# ibee.net
KiCad netlist of a schematic drawn in EAGLE
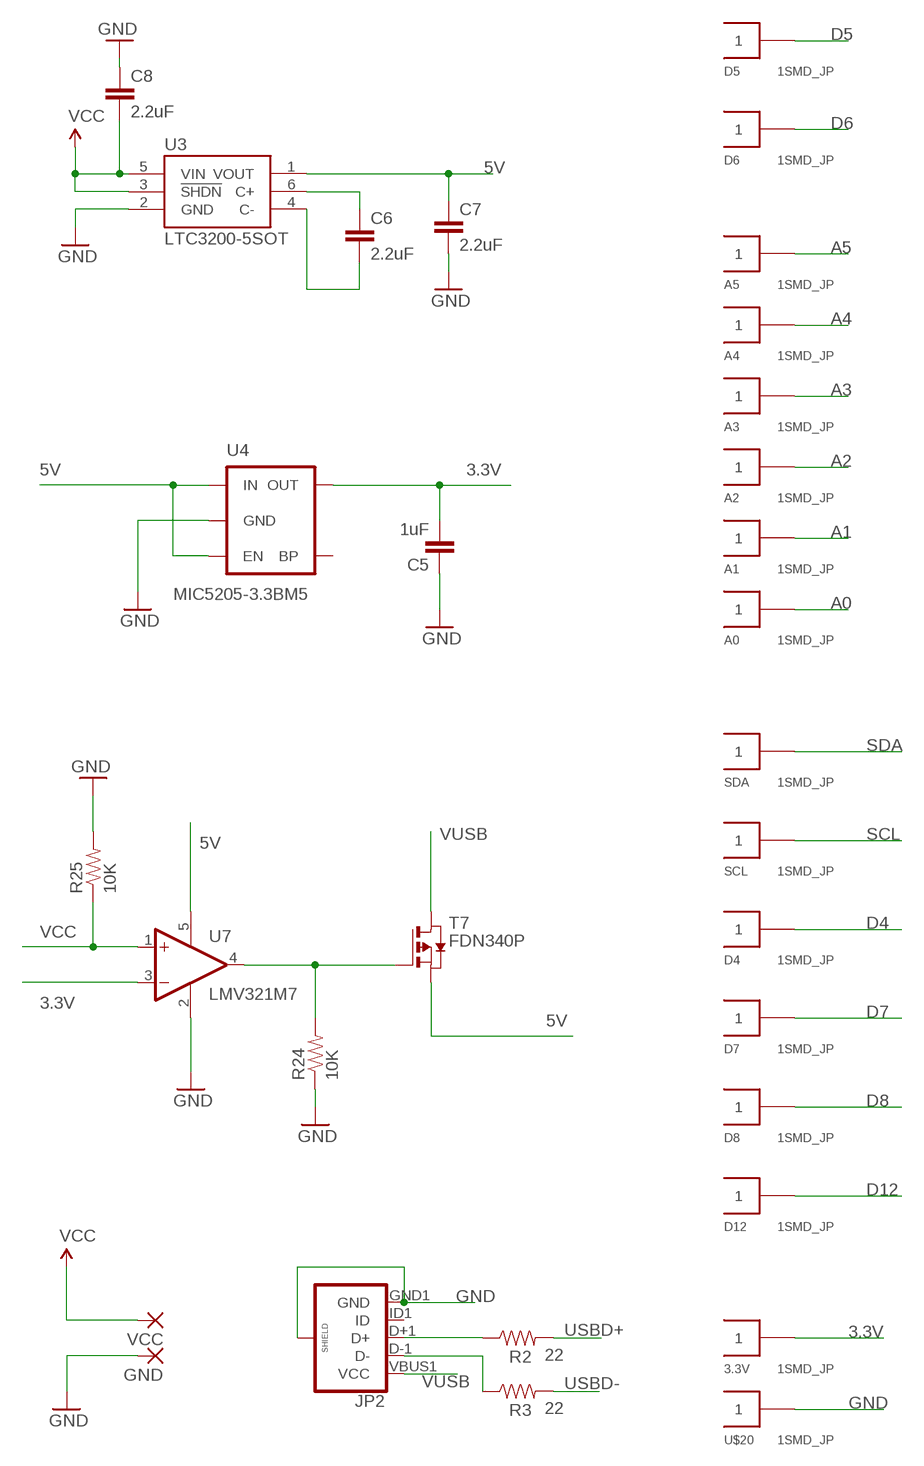
[diagram p0: schematic, sheet 1, part 1 of 2]
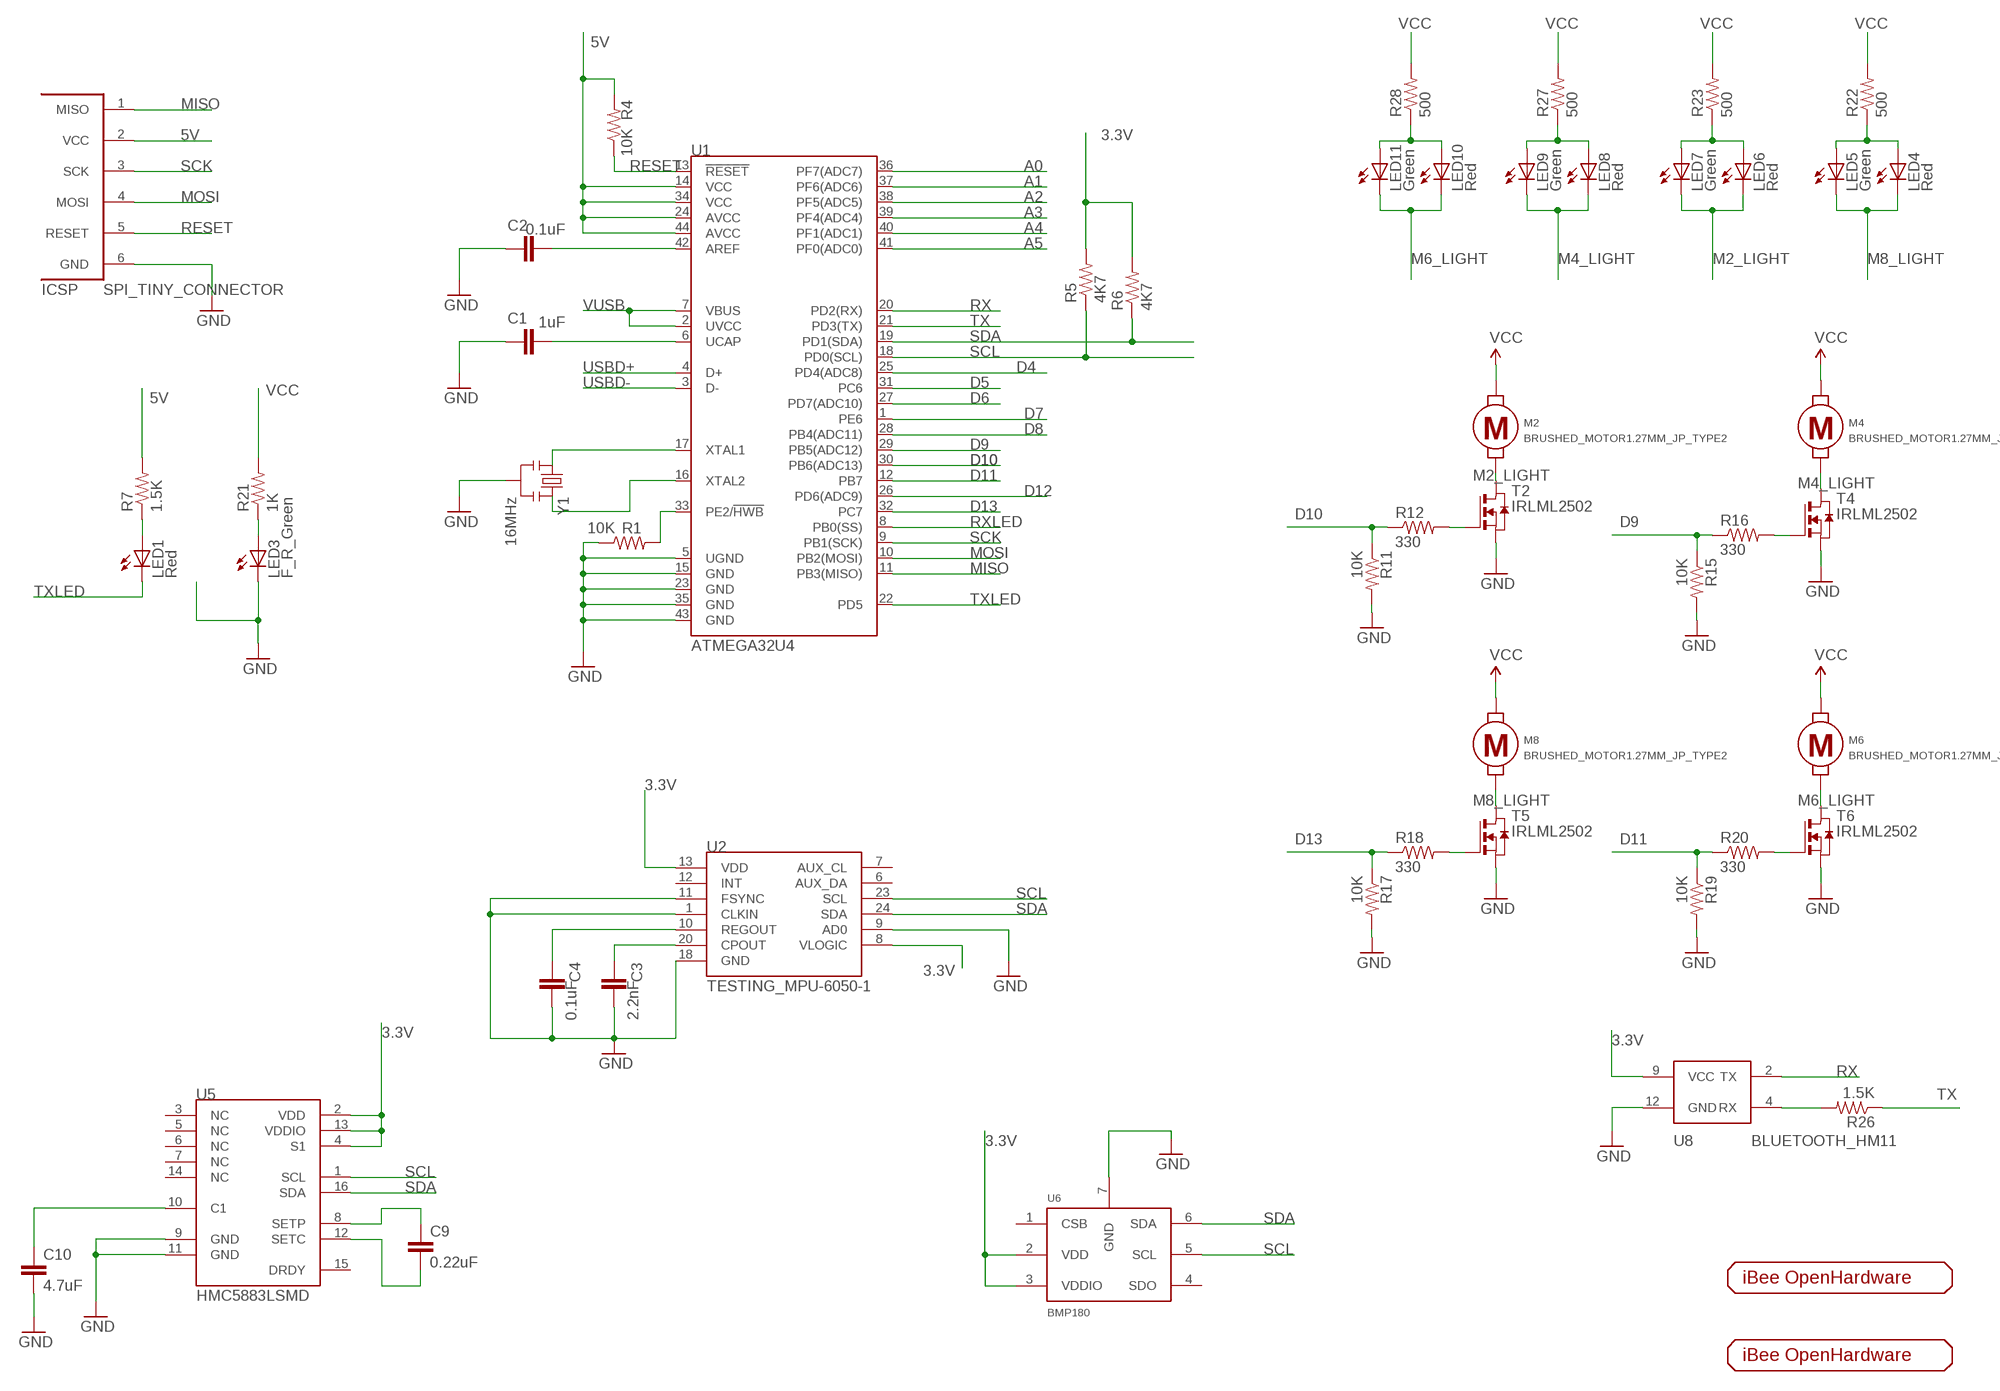
[diagram p1: schematic, sheet 1, part 2 of 2]

(export (version "E")
  (design (tool "Eeschema 10.0.6"))
  (components
    (comp (ref "3.3V")
      (value "1SMD_JP")
      (footprint "eagle-import:1SMD")
      (libsource (lib "eagle-import") (part "1SMD_JP"))
    )
    (comp (ref "A0")
      (value "1SMD_JP")
      (footprint "eagle-import:1SMD")
      (libsource (lib "eagle-import") (part "1SMD_JP"))
    )
    (comp (ref "A1")
      (value "1SMD_JP")
      (footprint "eagle-import:1SMD")
      (libsource (lib "eagle-import") (part "1SMD_JP"))
    )
    (comp (ref "A2")
      (value "1SMD_JP")
      (footprint "eagle-import:1SMD")
      (libsource (lib "eagle-import") (part "1SMD_JP"))
    )
    (comp (ref "A3")
      (value "1SMD_JP")
      (footprint "eagle-import:1SMD")
      (libsource (lib "eagle-import") (part "1SMD_JP"))
    )
    (comp (ref "A4")
      (value "1SMD_JP")
      (footprint "eagle-import:1SMD")
      (libsource (lib "eagle-import") (part "1SMD_JP"))
    )
    (comp (ref "A5")
      (value "1SMD_JP")
      (footprint "eagle-import:1SMD")
      (libsource (lib "eagle-import") (part "1SMD_JP"))
    )
    (comp (ref "C1")
      (value "1uF")
      (footprint "eagle-import:0402-CAP")
      (libsource (lib "eagle-import") (part "CAP0402-CAP"))
    )
    (comp (ref "C2")
      (value "0.1uF")
      (footprint "eagle-import:0402-CAP")
      (libsource (lib "eagle-import") (part "CAP0402-CAP"))
    )
    (comp (ref "C3")
      (value "2.2nF")
      (footprint "eagle-import:0402-CAP")
      (libsource (lib "eagle-import") (part "CAP0402-CAP"))
    )
    (comp (ref "C4")
      (value "0.1uF")
      (footprint "eagle-import:0402-CAP")
      (libsource (lib "eagle-import") (part "CAP0402-CAP"))
    )
    (comp (ref "C5")
      (value "1uF")
      (footprint "eagle-import:0402-CAP")
      (libsource (lib "eagle-import") (part "CAP0402-CAP"))
    )
    (comp (ref "C6")
      (value "2.2uF")
      (footprint "eagle-import:0603-CAP")
      (libsource (lib "eagle-import") (part "CAP0603-CAP"))
    )
    (comp (ref "C7")
      (value "2.2uF")
      (footprint "eagle-import:0603-CAP")
      (libsource (lib "eagle-import") (part "CAP0603-CAP"))
    )
    (comp (ref "C8")
      (value "2.2uF")
      (footprint "eagle-import:0603-CAP")
      (libsource (lib "eagle-import") (part "CAP0603-CAP"))
    )
    (comp (ref "C9")
      (value "0.22uF")
      (footprint "eagle-import:0402-CAP")
      (libsource (lib "eagle-import") (part "CAP0402-CAP"))
    )
    (comp (ref "C10")
      (value "4.7uF")
      (footprint "eagle-import:0603-CAP")
      (libsource (lib "eagle-import") (part "CAP0603-CAP"))
    )
    (comp (ref "D4")
      (value "1SMD_JP")
      (footprint "eagle-import:1SMD")
      (libsource (lib "eagle-import") (part "1SMD_JP"))
    )
    (comp (ref "D5")
      (value "1SMD_JP")
      (footprint "eagle-import:1SMD")
      (libsource (lib "eagle-import") (part "1SMD_JP"))
    )
    (comp (ref "D6")
      (value "1SMD_JP")
      (footprint "eagle-import:1SMD")
      (libsource (lib "eagle-import") (part "1SMD_JP"))
    )
    (comp (ref "D7")
      (value "1SMD_JP")
      (footprint "eagle-import:1SMD")
      (libsource (lib "eagle-import") (part "1SMD_JP"))
    )
    (comp (ref "D8")
      (value "1SMD_JP")
      (footprint "eagle-import:1SMD")
      (libsource (lib "eagle-import") (part "1SMD_JP"))
    )
    (comp (ref "D12")
      (value "1SMD_JP")
      (footprint "eagle-import:1SMD")
      (libsource (lib "eagle-import") (part "1SMD_JP"))
    )
    (comp (ref "GND")
      (value "2,15/1,0")
      (footprint "eagle-import:2,15_1,0")
      (libsource (lib "eagle-import") (part "2,15/1,0"))
    )
    (comp (ref "ICSP")
      (value "SPI_TINY_CONNECTOR")
      (footprint "eagle-import:AVR_ISP_TINY_CONNECTOR_NO_BORDER")
      (libsource (lib "eagle-import") (part "AVR_ISP_TINY_CONNECTORAVR_ISP_TINY_CONNCTOR_NO_BORDER"))
    )
    (comp (ref "JP2")
      (value "USB_MICROB_PLUGCONN-11752")
      (footprint "eagle-import:USB-B-MICRO-SMD_V03")
      (libsource (lib "eagle-import") (part "USB_MICROB_PLUGCONN-11752"))
    )
    (comp (ref "LED1")
      (value "Red")
      (footprint "eagle-import:CHIPLED_0603")
      (libsource (lib "eagle-import") (part "LEDCHIPLED_0603"))
    )
    (comp (ref "LED3")
      (value "F_R_Green")
      (footprint "eagle-import:CHIPLED_0603")
      (libsource (lib "eagle-import") (part "LEDCHIPLED_0603"))
    )
    (comp (ref "LED4")
      (value "Red")
      (footprint "eagle-import:CHIPLED_0603")
      (libsource (lib "eagle-import") (part "LEDCHIPLED_0603"))
    )
    (comp (ref "LED5")
      (value "Green")
      (footprint "eagle-import:CHIPLED_0603")
      (libsource (lib "eagle-import") (part "LEDCHIPLED_0603"))
    )
    (comp (ref "LED6")
      (value "Red")
      (footprint "eagle-import:CHIPLED_0603")
      (libsource (lib "eagle-import") (part "LEDCHIPLED_0603"))
    )
    (comp (ref "LED7")
      (value "Green")
      (footprint "eagle-import:CHIPLED_0603")
      (libsource (lib "eagle-import") (part "LEDCHIPLED_0603"))
    )
    (comp (ref "LED8")
      (value "Red")
      (footprint "eagle-import:CHIPLED_0603")
      (libsource (lib "eagle-import") (part "LEDCHIPLED_0603"))
    )
    (comp (ref "LED9")
      (value "Green")
      (footprint "eagle-import:CHIPLED_0603")
      (libsource (lib "eagle-import") (part "LEDCHIPLED_0603"))
    )
    (comp (ref "LED10")
      (value "Red")
      (footprint "eagle-import:CHIPLED_0603")
      (libsource (lib "eagle-import") (part "LEDCHIPLED_0603"))
    )
    (comp (ref "LED11")
      (value "Green")
      (footprint "eagle-import:CHIPLED_0603")
      (libsource (lib "eagle-import") (part "LEDCHIPLED_0603"))
    )
    (comp (ref "M2")
      (value "BRUSHED_MOTOR1.27MM_JP_TYPE2")
      (footprint "eagle-import:BRUSHED_MOTOR_1.27MM_JP_TYPE2")
      (libsource (lib "eagle-import") (part "BRUSHED_MOTOR1.27MM_JP_TYPE2"))
    )
    (comp (ref "M4")
      (value "BRUSHED_MOTOR1.27MM_JP")
      (footprint "eagle-import:BRUSHED_MOTOR_1.27MM_JP")
      (libsource (lib "eagle-import") (part "BRUSHED_MOTOR1.27MM_JP"))
    )
    (comp (ref "M6")
      (value "BRUSHED_MOTOR1.27MM_JP")
      (footprint "eagle-import:BRUSHED_MOTOR_1.27MM_JP")
      (libsource (lib "eagle-import") (part "BRUSHED_MOTOR1.27MM_JP"))
    )
    (comp (ref "M8")
      (value "BRUSHED_MOTOR1.27MM_JP_TYPE2")
      (footprint "eagle-import:BRUSHED_MOTOR_1.27MM_JP_TYPE2")
      (libsource (lib "eagle-import") (part "BRUSHED_MOTOR1.27MM_JP_TYPE2"))
    )
    (comp (ref "R1")
      (value "10K")
      (footprint "eagle-import:0402-RES")
      (libsource (lib "eagle-import") (part "RESISTOR0402-RES"))
    )
    (comp (ref "R2")
      (value "22")
      (footprint "eagle-import:0402-RES")
      (libsource (lib "eagle-import") (part "RESISTOR0402-RES"))
    )
    (comp (ref "R3")
      (value "22")
      (footprint "eagle-import:0402-RES")
      (libsource (lib "eagle-import") (part "RESISTOR0402-RES"))
    )
    (comp (ref "R4")
      (value "10K")
      (footprint "eagle-import:0402-RES")
      (libsource (lib "eagle-import") (part "RESISTOR0402-RES"))
    )
    (comp (ref "R5")
      (value "4K7")
      (footprint "eagle-import:0402-RES")
      (libsource (lib "eagle-import") (part "RESISTOR0402-RES"))
    )
    (comp (ref "R6")
      (value "4K7")
      (footprint "eagle-import:0402-RES")
      (libsource (lib "eagle-import") (part "RESISTOR0402-RES"))
    )
    (comp (ref "R7")
      (value "1.5K")
      (footprint "eagle-import:0402-RES")
      (libsource (lib "eagle-import") (part "RESISTOR0402-RES"))
    )
    (comp (ref "R11")
      (value "10K")
      (footprint "eagle-import:0402-RES")
      (libsource (lib "eagle-import") (part "RESISTOR0402-RES"))
    )
    (comp (ref "R12")
      (value "330")
      (footprint "eagle-import:0402-RES")
      (libsource (lib "eagle-import") (part "RESISTOR0402-RES"))
    )
    (comp (ref "R15")
      (value "10K")
      (footprint "eagle-import:0402-RES")
      (libsource (lib "eagle-import") (part "RESISTOR0402-RES"))
    )
    (comp (ref "R16")
      (value "330")
      (footprint "eagle-import:0402-RES")
      (libsource (lib "eagle-import") (part "RESISTOR0402-RES"))
    )
    (comp (ref "R17")
      (value "10K")
      (footprint "eagle-import:0402-RES")
      (libsource (lib "eagle-import") (part "RESISTOR0402-RES"))
    )
    (comp (ref "R18")
      (value "330")
      (footprint "eagle-import:0402-RES")
      (libsource (lib "eagle-import") (part "RESISTOR0402-RES"))
    )
    (comp (ref "R19")
      (value "10K")
      (footprint "eagle-import:0402-RES")
      (libsource (lib "eagle-import") (part "RESISTOR0402-RES"))
    )
    (comp (ref "R20")
      (value "330")
      (footprint "eagle-import:0402-RES")
      (libsource (lib "eagle-import") (part "RESISTOR0402-RES"))
    )
    (comp (ref "R21")
      (value "1K")
      (footprint "eagle-import:0402-RES")
      (libsource (lib "eagle-import") (part "RESISTOR0402-RES"))
    )
    (comp (ref "R22")
      (value "500")
      (footprint "eagle-import:0402-RES")
      (libsource (lib "eagle-import") (part "RESISTOR0402-RES"))
    )
    (comp (ref "R23")
      (value "500")
      (footprint "eagle-import:0402-RES")
      (libsource (lib "eagle-import") (part "RESISTOR0402-RES"))
    )
    (comp (ref "R24")
      (value "10K")
      (footprint "eagle-import:0402-RES")
      (libsource (lib "eagle-import") (part "RESISTOR0402-RES"))
    )
    (comp (ref "R25")
      (value "10K")
      (footprint "eagle-import:0402-RES")
      (libsource (lib "eagle-import") (part "RESISTOR0402-RES"))
    )
    (comp (ref "R26")
      (value "1.5K")
      (footprint "eagle-import:0402-RES")
      (libsource (lib "eagle-import") (part "RESISTOR0402-RES"))
    )
    (comp (ref "R27")
      (value "500")
      (footprint "eagle-import:0402-RES")
      (libsource (lib "eagle-import") (part "RESISTOR0402-RES"))
    )
    (comp (ref "R28")
      (value "500")
      (footprint "eagle-import:0402-RES")
      (libsource (lib "eagle-import") (part "RESISTOR0402-RES"))
    )
    (comp (ref "SCL")
      (value "1SMD_JP")
      (footprint "eagle-import:1SMD")
      (libsource (lib "eagle-import") (part "1SMD_JP"))
    )
    (comp (ref "SDA")
      (value "1SMD_JP")
      (footprint "eagle-import:1SMD")
      (libsource (lib "eagle-import") (part "1SMD_JP"))
    )
    (comp (ref "T2")
      (value "IRLML2502")
      (footprint "eagle-import:SOT-23")
      (libsource (lib "eagle-import") (part "NMOSSOT23"))
    )
    (comp (ref "T4")
      (value "IRLML2502")
      (footprint "eagle-import:SOT-23")
      (libsource (lib "eagle-import") (part "NMOSSOT23"))
    )
    (comp (ref "T5")
      (value "IRLML2502")
      (footprint "eagle-import:SOT-23")
      (libsource (lib "eagle-import") (part "NMOSSOT23"))
    )
    (comp (ref "T6")
      (value "IRLML2502")
      (footprint "eagle-import:SOT-23")
      (libsource (lib "eagle-import") (part "NMOSSOT23"))
    )
    (comp (ref "T7")
      (value "FDN340P")
      (footprint "eagle-import:SOT23")
      (libsource (lib "eagle-import") (part "FDN340P"))
    )
    (comp (ref "U$1")
      (value "IBEE-LOGO-T")
      (footprint "eagle-import:IBEE-LOGO-TOP")
      (libsource (lib "eagle-import") (part "IBEE-LOGO-T"))
    )
    (comp (ref "U$2")
      (value "IBEE-LOGO-B")
      (footprint "eagle-import:FLEXBOT_LOGO_TYPE2")
      (libsource (lib "eagle-import") (part "IBEE-LOGO-B"))
    )
    (comp (ref "U$20")
      (value "1SMD_JP")
      (footprint "eagle-import:1SMD")
      (libsource (lib "eagle-import") (part "1SMD_JP"))
    )
    (comp (ref "U1")
      (value "ATMEGA32U4")
      (footprint "eagle-import:TESTING_QFN-44-7X7")
      (libsource (lib "eagle-import") (part "ATMEGA32U4"))
    )
    (comp (ref "U2")
      (value "TESTING_MPU-6050-1")
      (footprint "eagle-import:TESTING_QFN-24-4MM2")
      (libsource (lib "eagle-import") (part "TESTING_MPU-6050-1"))
    )
    (comp (ref "U3")
      (value "LTC3200-5SOT")
      (footprint "eagle-import:SOT23-6")
      (libsource (lib "eagle-import") (part "LTC3200-5SOT"))
    )
    (comp (ref "U4")
      (value "MIC5205-3.3BM5")
      (footprint "eagle-import:SOT23-5")
      (libsource (lib "eagle-import") (part "MIC52053.3V"))
    )
    (comp (ref "U5")
      (value "HMC5883LSMD")
      (footprint "eagle-import:TESTING_16LPCC")
      (libsource (lib "eagle-import") (part "HMC5883LSMD"))
    )
    (comp (ref "U6")
      (value "BMP180")
      (footprint "eagle-import:BMP180")
      (libsource (lib "eagle-import") (part "BMP180"))
    )
    (comp (ref "U7")
      (value "LMV321M7")
      (footprint "eagle-import:SC70-5L")
      (libsource (lib "eagle-import") (part "LMV321?M7"))
    )
    (comp (ref "U8")
      (value "BLUETOOTH_HM11")
      (footprint "eagle-import:BLUETOOTH_HM11")
      (libsource (lib "eagle-import") (part "BLUETOOTH_HM11"))
    )
    (comp (ref "VCC")
      (value "2,15/1,0")
      (footprint "eagle-import:2,15_1,0")
      (libsource (lib "eagle-import") (part "2,15/1,0"))
    )
    (comp (ref "Y1")
      (value "16MHz")
      (footprint "eagle-import:RESONATOR-SMD")
      (libsource (lib "eagle-import") (part "RESONATOR16MHZ"))
    )
  )
  (nets
    (net (code "1") (name "/3.3V") (class "Default")
      (node (ref "3.3V") (pin "1") (pinfunction "1_1") (pintype "bidirectional"))
      (node (ref "C5") (pin "2") (pinfunction "2_2") (pintype "passive"))
      (node (ref "R5") (pin "2") (pinfunction "2_2") (pintype "passive"))
      (node (ref "R6") (pin "2") (pinfunction "2_2") (pintype "passive"))
      (node (ref "U2") (pin "13") (pinfunction "VDD_13") (pintype "bidirectional"))
      (node (ref "U2") (pin "8") (pinfunction "VLOGIC_8") (pintype "bidirectional"))
      (node (ref "U4") (pin "5") (pinfunction "OUT_5") (pintype "passive"))
      (node (ref "U5") (pin "13") (pinfunction "VDDIO_13") (pintype "bidirectional"))
      (node (ref "U5") (pin "2") (pinfunction "VDD_2") (pintype "bidirectional"))
      (node (ref "U5") (pin "4") (pinfunction "S1_4") (pintype "bidirectional"))
      (node (ref "U6") (pin "2") (pinfunction "VDD_2") (pintype "bidirectional"))
      (node (ref "U6") (pin "3") (pinfunction "VDDIO_3") (pintype "bidirectional"))
      (node (ref "U7") (pin "3") (pinfunction "-IN_3") (pintype "input"))
      (node (ref "U8") (pin "9") (pinfunction "VCC_9") (pintype "bidirectional"))
    )
    (net (code "2") (name "/5V") (class "Default")
      (node (ref "C7") (pin "1") (pinfunction "1_1") (pintype "passive"))
      (node (ref "ICSP") (pin "2") (pinfunction "VCC_2") (pintype "bidirectional"))
      (node (ref "R4") (pin "2") (pinfunction "2_2") (pintype "passive"))
      (node (ref "R7") (pin "2") (pinfunction "2_2") (pintype "passive"))
      (node (ref "T7") (pin "2") (pinfunction "S_2") (pintype "passive"))
      (node (ref "U1") (pin "14") (pinfunction "VCC_14") (pintype "bidirectional"))
      (node (ref "U1") (pin "24") (pinfunction "AVCC_24") (pintype "bidirectional"))
      (node (ref "U1") (pin "34") (pinfunction "VCC_34") (pintype "bidirectional"))
      (node (ref "U1") (pin "44") (pinfunction "AVCC_44") (pintype "bidirectional"))
      (node (ref "U3") (pin "1") (pinfunction "VOUT_1") (pintype "bidirectional"))
      (node (ref "U4") (pin "1") (pinfunction "IN_1") (pintype "input"))
      (node (ref "U4") (pin "3") (pinfunction "EN_3") (pintype "input"))
      (node (ref "U7") (pin "5") (pinfunction "V+_5") (pintype "power_in"))
    )
    (net (code "3") (name "/A0") (class "Default")
      (node (ref "A0") (pin "1") (pinfunction "1_1") (pintype "bidirectional"))
      (node (ref "U1") (pin "36") (pinfunction "PF7(ADC7)_36") (pintype "bidirectional"))
    )
    (net (code "4") (name "/A1") (class "Default")
      (node (ref "A1") (pin "1") (pinfunction "1_1") (pintype "bidirectional"))
      (node (ref "U1") (pin "37") (pinfunction "PF6(ADC6)_37") (pintype "bidirectional"))
    )
    (net (code "5") (name "/A2") (class "Default")
      (node (ref "A2") (pin "1") (pinfunction "1_1") (pintype "bidirectional"))
      (node (ref "U1") (pin "38") (pinfunction "PF5(ADC5)_38") (pintype "bidirectional"))
    )
    (net (code "6") (name "/A3") (class "Default")
      (node (ref "A3") (pin "1") (pinfunction "1_1") (pintype "bidirectional"))
      (node (ref "U1") (pin "39") (pinfunction "PF4(ADC4)_39") (pintype "bidirectional"))
    )
    (net (code "7") (name "/A4") (class "Default")
      (node (ref "A4") (pin "1") (pinfunction "1_1") (pintype "bidirectional"))
      (node (ref "U1") (pin "40") (pinfunction "PF1(ADC1)_40") (pintype "bidirectional"))
    )
    (net (code "8") (name "/A5") (class "Default")
      (node (ref "A5") (pin "1") (pinfunction "1_1") (pintype "bidirectional"))
      (node (ref "U1") (pin "41") (pinfunction "PF0(ADC0)_41") (pintype "bidirectional"))
    )
    (net (code "9") (name "/D4") (class "Default")
      (node (ref "D4") (pin "1") (pinfunction "1_1") (pintype "bidirectional"))
      (node (ref "U1") (pin "25") (pinfunction "PD4(ADC8)_25") (pintype "bidirectional"))
    )
    (net (code "10") (name "/D5") (class "Default")
      (node (ref "D5") (pin "1") (pinfunction "1_1") (pintype "bidirectional"))
      (node (ref "U1") (pin "31") (pinfunction "PC6_31") (pintype "bidirectional"))
    )
    (net (code "11") (name "/D6") (class "Default")
      (node (ref "D6") (pin "1") (pinfunction "1_1") (pintype "bidirectional"))
      (node (ref "U1") (pin "27") (pinfunction "PD7(ADC10)_27") (pintype "bidirectional"))
    )
    (net (code "12") (name "/D7") (class "Default")
      (node (ref "D7") (pin "1") (pinfunction "1_1") (pintype "bidirectional"))
      (node (ref "U1") (pin "1") (pinfunction "PE6_1") (pintype "bidirectional"))
    )
    (net (code "13") (name "/D8") (class "Default")
      (node (ref "D8") (pin "1") (pinfunction "1_1") (pintype "bidirectional"))
      (node (ref "U1") (pin "28") (pinfunction "PB4(ADC11)_28") (pintype "bidirectional"))
    )
    (net (code "14") (name "/D9") (class "Default")
      (node (ref "R15") (pin "1") (pinfunction "1_1") (pintype "passive"))
      (node (ref "R16") (pin "1") (pinfunction "1_1") (pintype "passive"))
      (node (ref "U1") (pin "29") (pinfunction "PB5(ADC12)_29") (pintype "bidirectional"))
    )
    (net (code "15") (name "/D10") (class "Default")
      (node (ref "R11") (pin "1") (pinfunction "1_1") (pintype "passive"))
      (node (ref "R12") (pin "1") (pinfunction "1_1") (pintype "passive"))
      (node (ref "U1") (pin "30") (pinfunction "PB6(ADC13)_30") (pintype "bidirectional"))
    )
    (net (code "16") (name "/D11") (class "Default")
      (node (ref "R19") (pin "1") (pinfunction "1_1") (pintype "passive"))
      (node (ref "R20") (pin "1") (pinfunction "1_1") (pintype "passive"))
      (node (ref "U1") (pin "12") (pinfunction "PB7_12") (pintype "bidirectional"))
    )
    (net (code "17") (name "/D12") (class "Default")
      (node (ref "D12") (pin "1") (pinfunction "1_1") (pintype "bidirectional"))
      (node (ref "U1") (pin "26") (pinfunction "PD6(ADC9)_26") (pintype "bidirectional"))
    )
    (net (code "18") (name "/D13") (class "Default")
      (node (ref "R17") (pin "1") (pinfunction "1_1") (pintype "passive"))
      (node (ref "R18") (pin "1") (pinfunction "1_1") (pintype "passive"))
      (node (ref "U1") (pin "32") (pinfunction "PC7_32") (pintype "bidirectional"))
    )
    (net (code "19") (name "/M2_LIGHT") (class "Default")
      (node (ref "LED6") (pin "C") (pinfunction "C_C") (pintype "passive"))
      (node (ref "LED7") (pin "C") (pinfunction "C_C") (pintype "passive"))
      (node (ref "M2") (pin "P$1") (pinfunction "1_P$1") (pintype "bidirectional"))
      (node (ref "T2") (pin "1") (pinfunction "D_1") (pintype "passive"))
    )
    (net (code "20") (name "/M4_LIGHT") (class "Default")
      (node (ref "LED8") (pin "C") (pinfunction "C_C") (pintype "passive"))
      (node (ref "LED9") (pin "C") (pinfunction "C_C") (pintype "passive"))
      (node (ref "M4") (pin "P$1") (pinfunction "1_P$1") (pintype "bidirectional"))
      (node (ref "T4") (pin "1") (pinfunction "D_1") (pintype "passive"))
    )
    (net (code "21") (name "/M6_LIGHT") (class "Default")
      (node (ref "LED10") (pin "C") (pinfunction "C_C") (pintype "passive"))
      (node (ref "LED11") (pin "C") (pinfunction "C_C") (pintype "passive"))
      (node (ref "M6") (pin "P$1") (pinfunction "1_P$1") (pintype "bidirectional"))
      (node (ref "T6") (pin "1") (pinfunction "D_1") (pintype "passive"))
    )
    (net (code "22") (name "/M8_LIGHT") (class "Default")
      (node (ref "LED4") (pin "C") (pinfunction "C_C") (pintype "passive"))
      (node (ref "LED5") (pin "C") (pinfunction "C_C") (pintype "passive"))
      (node (ref "M8") (pin "P$1") (pinfunction "1_P$1") (pintype "bidirectional"))
      (node (ref "T5") (pin "1") (pinfunction "D_1") (pintype "passive"))
    )
    (net (code "23") (name "/MISO") (class "Default")
      (node (ref "ICSP") (pin "1") (pinfunction "MISO_1") (pintype "bidirectional"))
      (node (ref "U1") (pin "11") (pinfunction "PB3(MISO)_11") (pintype "bidirectional"))
    )
    (net (code "24") (name "/MOSI") (class "Default")
      (node (ref "ICSP") (pin "4") (pinfunction "MOSI_4") (pintype "bidirectional"))
      (node (ref "U1") (pin "10") (pinfunction "PB2(MOSI)_10") (pintype "bidirectional"))
    )
    (net (code "25") (name "/RESET") (class "Default")
      (node (ref "ICSP") (pin "5") (pinfunction "RESET_5") (pintype "bidirectional"))
      (node (ref "R4") (pin "1") (pinfunction "1_1") (pintype "passive"))
      (node (ref "U1") (pin "13") (pinfunction "~{RESET}_13") (pintype "bidirectional"))
    )
    (net (code "26") (name "/RX") (class "Default")
      (node (ref "U1") (pin "20") (pinfunction "PD2(RX)_20") (pintype "bidirectional"))
      (node (ref "U8") (pin "2") (pinfunction "TX_2") (pintype "bidirectional"))
    )
    (net (code "27") (name "/RXLED") (class "Default")
      (node (ref "U1") (pin "8") (pinfunction "PB0(SS)_8") (pintype "bidirectional"))
    )
    (net (code "28") (name "/SCK") (class "Default")
      (node (ref "ICSP") (pin "3") (pinfunction "SCK_3") (pintype "bidirectional"))
      (node (ref "U1") (pin "9") (pinfunction "PB1(SCK)_9") (pintype "bidirectional"))
    )
    (net (code "29") (name "/SCL") (class "Default")
      (node (ref "R5") (pin "1") (pinfunction "1_1") (pintype "passive"))
      (node (ref "SCL") (pin "1") (pinfunction "1_1") (pintype "bidirectional"))
      (node (ref "U1") (pin "18") (pinfunction "PD0(SCL)_18") (pintype "bidirectional"))
      (node (ref "U2") (pin "23") (pinfunction "SCL_23") (pintype "bidirectional"))
      (node (ref "U5") (pin "1") (pinfunction "SCL_1") (pintype "bidirectional"))
      (node (ref "U6") (pin "5") (pinfunction "SCL_5") (pintype "bidirectional"))
    )
    (net (code "30") (name "/SDA") (class "Default")
      (node (ref "R6") (pin "1") (pinfunction "1_1") (pintype "passive"))
      (node (ref "SDA") (pin "1") (pinfunction "1_1") (pintype "bidirectional"))
      (node (ref "U1") (pin "19") (pinfunction "PD1(SDA)_19") (pintype "bidirectional"))
      (node (ref "U2") (pin "24") (pinfunction "SDA_24") (pintype "bidirectional"))
      (node (ref "U5") (pin "16") (pinfunction "SDA_16") (pintype "bidirectional"))
      (node (ref "U6") (pin "6") (pinfunction "SDA_6") (pintype "bidirectional"))
    )
    (net (code "31") (name "/TX") (class "Default")
      (node (ref "R26") (pin "1") (pinfunction "1_1") (pintype "passive"))
      (node (ref "U1") (pin "21") (pinfunction "PD3(TX)_21") (pintype "bidirectional"))
    )
    (net (code "32") (name "/TXLED") (class "Default")
      (node (ref "LED1") (pin "C") (pinfunction "C_C") (pintype "passive"))
      (node (ref "U1") (pin "22") (pinfunction "PD5_22") (pintype "bidirectional"))
    )
    (net (code "33") (name "/USBD+") (class "Default")
      (node (ref "R2") (pin "2") (pinfunction "2_2") (pintype "passive"))
      (node (ref "U1") (pin "4") (pinfunction "D+_4") (pintype "bidirectional"))
    )
    (net (code "34") (name "/USBD-") (class "Default")
      (node (ref "R3") (pin "2") (pinfunction "2_2") (pintype "passive"))
      (node (ref "U1") (pin "3") (pinfunction "D-_3") (pintype "bidirectional"))
    )
    (net (code "35") (name "/VUSB") (class "Default")
      (node (ref "JP2") (pin "VBUS1") (pinfunction "VCC_VBUS1") (pintype "bidirectional"))
      (node (ref "T7") (pin "1") (pinfunction "D_1") (pintype "passive"))
      (node (ref "U1") (pin "2") (pinfunction "UVCC_2") (pintype "bidirectional"))
      (node (ref "U1") (pin "7") (pinfunction "VBUS_7") (pintype "bidirectional"))
    )
    (net (code "36") (name "GND") (class "Default")
      (node (ref "C1") (pin "1") (pinfunction "1_1") (pintype "passive"))
      (node (ref "C10") (pin "2") (pinfunction "2_2") (pintype "passive"))
      (node (ref "C2") (pin "1") (pinfunction "1_1") (pintype "passive"))
      (node (ref "C3") (pin "2") (pinfunction "2_2") (pintype "passive"))
      (node (ref "C4") (pin "2") (pinfunction "2_2") (pintype "passive"))
      (node (ref "C5") (pin "1") (pinfunction "1_1") (pintype "passive"))
      (node (ref "C7") (pin "2") (pinfunction "2_2") (pintype "passive"))
      (node (ref "C8") (pin "1") (pinfunction "1_1") (pintype "passive"))
      (node (ref "GND") (pin "1") (pinfunction "P_1") (pintype "passive"))
      (node (ref "ICSP") (pin "6") (pinfunction "GND_6") (pintype "bidirectional"))
      (node (ref "JP2") (pin "GND1") (pinfunction "GND_GND1") (pintype "bidirectional"))
      (node (ref "JP2") (pin "SHIELD1") (pinfunction "SHIELD_SHIELD1") (pintype "bidirectional"))
      (node (ref "JP2") (pin "SHIELD2") (pinfunction "SHIELD_SHIELD2") (pintype "bidirectional"))
      (node (ref "JP2") (pin "SHIELD3") (pinfunction "SHIELD_SHIELD3") (pintype "bidirectional"))
      (node (ref "LED3") (pin "C") (pinfunction "C_C") (pintype "passive"))
      (node (ref "R1") (pin "1") (pinfunction "1_1") (pintype "passive"))
      (node (ref "R11") (pin "2") (pinfunction "2_2") (pintype "passive"))
      (node (ref "R15") (pin "2") (pinfunction "2_2") (pintype "passive"))
      (node (ref "R17") (pin "2") (pinfunction "2_2") (pintype "passive"))
      (node (ref "R19") (pin "2") (pinfunction "2_2") (pintype "passive"))
      (node (ref "R24") (pin "1") (pinfunction "1_1") (pintype "passive"))
      (node (ref "R25") (pin "2") (pinfunction "2_2") (pintype "passive"))
      (node (ref "T2") (pin "2") (pinfunction "S_2") (pintype "passive"))
      (node (ref "T4") (pin "2") (pinfunction "S_2") (pintype "passive"))
      (node (ref "T5") (pin "2") (pinfunction "S_2") (pintype "passive"))
      (node (ref "T6") (pin "2") (pinfunction "S_2") (pintype "passive"))
      (node (ref "U$20") (pin "1") (pinfunction "1_1") (pintype "bidirectional"))
      (node (ref "U1") (pin "15") (pinfunction "GND_15") (pintype "bidirectional"))
      (node (ref "U1") (pin "23") (pinfunction "GND_23") (pintype "bidirectional"))
      (node (ref "U1") (pin "35") (pinfunction "GND_35") (pintype "bidirectional"))
      (node (ref "U1") (pin "43") (pinfunction "GND_43") (pintype "bidirectional"))
      (node (ref "U1") (pin "5") (pinfunction "UGND_5") (pintype "bidirectional"))
      (node (ref "U2") (pin "1") (pinfunction "CLKIN_1") (pintype "bidirectional"))
      (node (ref "U2") (pin "11") (pinfunction "FSYNC_11") (pintype "bidirectional"))
      (node (ref "U2") (pin "18") (pinfunction "GND_18") (pintype "bidirectional"))
      (node (ref "U2") (pin "9") (pinfunction "AD0_9") (pintype "bidirectional"))
      (node (ref "U3") (pin "2") (pinfunction "GND_2") (pintype "bidirectional"))
      (node (ref "U4") (pin "2") (pinfunction "GND_2") (pintype "input"))
      (node (ref "U5") (pin "11") (pinfunction "GND_11") (pintype "bidirectional"))
      (node (ref "U5") (pin "9") (pinfunction "GND_9") (pintype "bidirectional"))
      (node (ref "U6") (pin "7") (pinfunction "GND_7") (pintype "bidirectional"))
      (node (ref "U7") (pin "2") (pinfunction "V-_2") (pintype "power_in"))
      (node (ref "U8") (pin "12") (pinfunction "GND_12") (pintype "bidirectional"))
      (node (ref "Y1") (pin "2") (pinfunction "2_2") (pintype "passive"))
    )
    (net (code "37") (name "Net-(JP2-D+)") (class "Default")
      (node (ref "JP2") (pin "D+1") (pinfunction "D+_D+1") (pintype "bidirectional"))
      (node (ref "R2") (pin "1") (pinfunction "1_1") (pintype "passive"))
    )
    (net (code "38") (name "Net-(JP2-D-)") (class "Default")
      (node (ref "JP2") (pin "D-1") (pinfunction "D-_D-1") (pintype "bidirectional"))
      (node (ref "R3") (pin "1") (pinfunction "1_1") (pintype "passive"))
    )
    (net (code "39") (name "Net-(LED1-PadA)") (class "Default")
      (node (ref "LED1") (pin "A") (pinfunction "A_A") (pintype "passive"))
      (node (ref "R7") (pin "1") (pinfunction "1_1") (pintype "passive"))
    )
    (net (code "40") (name "Net-(LED3-PadA)") (class "Default")
      (node (ref "LED3") (pin "A") (pinfunction "A_A") (pintype "passive"))
      (node (ref "R21") (pin "1") (pinfunction "1_1") (pintype "passive"))
    )
    (net (code "41") (name "Net-(LED4-PadA)") (class "Default")
      (node (ref "LED4") (pin "A") (pinfunction "A_A") (pintype "passive"))
      (node (ref "LED5") (pin "A") (pinfunction "A_A") (pintype "passive"))
      (node (ref "R22") (pin "1") (pinfunction "1_1") (pintype "passive"))
    )
    (net (code "42") (name "Net-(LED6-PadA)") (class "Default")
      (node (ref "LED6") (pin "A") (pinfunction "A_A") (pintype "passive"))
      (node (ref "LED7") (pin "A") (pinfunction "A_A") (pintype "passive"))
      (node (ref "R23") (pin "1") (pinfunction "1_1") (pintype "passive"))
    )
    (net (code "43") (name "Net-(LED8-PadA)") (class "Default")
      (node (ref "LED8") (pin "A") (pinfunction "A_A") (pintype "passive"))
      (node (ref "LED9") (pin "A") (pinfunction "A_A") (pintype "passive"))
      (node (ref "R27") (pin "1") (pinfunction "1_1") (pintype "passive"))
    )
    (net (code "44") (name "Net-(LED10-PadA)") (class "Default")
      (node (ref "LED10") (pin "A") (pinfunction "A_A") (pintype "passive"))
      (node (ref "LED11") (pin "A") (pinfunction "A_A") (pintype "passive"))
      (node (ref "R28") (pin "1") (pinfunction "1_1") (pintype "passive"))
    )
    (net (code "45") (name "Net-(T2-G)") (class "Default")
      (node (ref "R12") (pin "2") (pinfunction "2_2") (pintype "passive"))
      (node (ref "T2") (pin "3") (pinfunction "G_3") (pintype "passive"))
    )
    (net (code "46") (name "Net-(T4-G)") (class "Default")
      (node (ref "R16") (pin "2") (pinfunction "2_2") (pintype "passive"))
      (node (ref "T4") (pin "3") (pinfunction "G_3") (pintype "passive"))
    )
    (net (code "47") (name "Net-(T5-G)") (class "Default")
      (node (ref "R18") (pin "2") (pinfunction "2_2") (pintype "passive"))
      (node (ref "T5") (pin "3") (pinfunction "G_3") (pintype "passive"))
    )
    (net (code "48") (name "Net-(T6-G)") (class "Default")
      (node (ref "R20") (pin "2") (pinfunction "2_2") (pintype "passive"))
      (node (ref "T6") (pin "3") (pinfunction "G_3") (pintype "passive"))
    )
    (net (code "49") (name "Net-(T7-G)") (class "Default")
      (node (ref "R24") (pin "2") (pinfunction "2_2") (pintype "passive"))
      (node (ref "T7") (pin "3") (pinfunction "G_3") (pintype "passive"))
      (node (ref "U7") (pin "4") (pinfunction "OUT_4") (pintype "output"))
    )
    (net (code "50") (name "Net-(U1-AREF)") (class "Default")
      (node (ref "C2") (pin "2") (pinfunction "2_2") (pintype "passive"))
      (node (ref "U1") (pin "42") (pinfunction "AREF_42") (pintype "bidirectional"))
    )
    (net (code "51") (name "Net-(U1-PE2{slash}~{HWB})") (class "Default")
      (node (ref "R1") (pin "2") (pinfunction "2_2") (pintype "passive"))
      (node (ref "U1") (pin "33") (pinfunction "PE2/~{HWB}_33") (pintype "bidirectional"))
    )
    (net (code "52") (name "Net-(U1-UCAP)") (class "Default")
      (node (ref "C1") (pin "2") (pinfunction "2_2") (pintype "passive"))
      (node (ref "U1") (pin "6") (pinfunction "UCAP_6") (pintype "bidirectional"))
    )
    (net (code "53") (name "Net-(U1-XTAL1)") (class "Default")
      (node (ref "U1") (pin "17") (pinfunction "XTAL1_17") (pintype "bidirectional"))
      (node (ref "Y1") (pin "1") (pinfunction "1_1") (pintype "passive"))
    )
    (net (code "54") (name "Net-(U1-XTAL2)") (class "Default")
      (node (ref "U1") (pin "16") (pinfunction "XTAL2_16") (pintype "bidirectional"))
      (node (ref "Y1") (pin "3") (pinfunction "3_3") (pintype "passive"))
    )
    (net (code "55") (name "Net-(U2-CPOUT)") (class "Default")
      (node (ref "C3") (pin "1") (pinfunction "1_1") (pintype "passive"))
      (node (ref "U2") (pin "20") (pinfunction "CPOUT_20") (pintype "bidirectional"))
    )
    (net (code "56") (name "Net-(U2-REGOUT)") (class "Default")
      (node (ref "C4") (pin "1") (pinfunction "1_1") (pintype "passive"))
      (node (ref "U2") (pin "10") (pinfunction "REGOUT_10") (pintype "bidirectional"))
    )
    (net (code "57") (name "Net-(U3-C+)") (class "Default")
      (node (ref "C6") (pin "1") (pinfunction "1_1") (pintype "passive"))
      (node (ref "U3") (pin "6") (pinfunction "C+_6") (pintype "bidirectional"))
    )
    (net (code "58") (name "Net-(U3-C-)") (class "Default")
      (node (ref "C6") (pin "2") (pinfunction "2_2") (pintype "passive"))
      (node (ref "U3") (pin "4") (pinfunction "C-_4") (pintype "bidirectional"))
    )
    (net (code "59") (name "Net-(U5-C1)") (class "Default")
      (node (ref "C10") (pin "1") (pinfunction "1_1") (pintype "passive"))
      (node (ref "U5") (pin "10") (pinfunction "C1_10") (pintype "bidirectional"))
    )
    (net (code "60") (name "Net-(U5-SETC)") (class "Default")
      (node (ref "C9") (pin "2") (pinfunction "2_2") (pintype "passive"))
      (node (ref "U5") (pin "12") (pinfunction "SETC_12") (pintype "bidirectional"))
    )
    (net (code "61") (name "Net-(U5-SETP)") (class "Default")
      (node (ref "C9") (pin "1") (pinfunction "1_1") (pintype "passive"))
      (node (ref "U5") (pin "8") (pinfunction "SETP_8") (pintype "bidirectional"))
    )
    (net (code "62") (name "Net-(U8-RX)") (class "Default")
      (node (ref "R26") (pin "2") (pinfunction "2_2") (pintype "passive"))
      (node (ref "U8") (pin "4") (pinfunction "RX_4") (pintype "bidirectional"))
    )
    (net (code "63") (name "VCC") (class "Default")
      (node (ref "C8") (pin "2") (pinfunction "2_2") (pintype "passive"))
      (node (ref "M2") (pin "P$2") (pinfunction "2_P$2") (pintype "bidirectional"))
      (node (ref "M4") (pin "P$2") (pinfunction "2_P$2") (pintype "bidirectional"))
      (node (ref "M6") (pin "P$2") (pinfunction "2_P$2") (pintype "bidirectional"))
      (node (ref "M8") (pin "P$2") (pinfunction "2_P$2") (pintype "bidirectional"))
      (node (ref "R21") (pin "2") (pinfunction "2_2") (pintype "passive"))
      (node (ref "R22") (pin "2") (pinfunction "2_2") (pintype "passive"))
      (node (ref "R23") (pin "2") (pinfunction "2_2") (pintype "passive"))
      (node (ref "R25") (pin "1") (pinfunction "1_1") (pintype "passive"))
      (node (ref "R27") (pin "2") (pinfunction "2_2") (pintype "passive"))
      (node (ref "R28") (pin "2") (pinfunction "2_2") (pintype "passive"))
      (node (ref "U3") (pin "3") (pinfunction "~{SHDN}_3") (pintype "bidirectional"))
      (node (ref "U3") (pin "5") (pinfunction "VIN_5") (pintype "bidirectional"))
      (node (ref "U7") (pin "1") (pinfunction "+IN_1") (pintype "input"))
      (node (ref "VCC") (pin "1") (pinfunction "P_1") (pintype "passive"))
    )
    (net (code "64") (name "unconnected-(JP2-ID-PadID1)") (class "Default")
      (node (ref "JP2") (pin "ID1") (pinfunction "ID_ID1") (pintype "bidirectional"))
    )
    (net (code "65") (name "unconnected-(U2-AUX_CL-Pad7)") (class "Default")
      (node (ref "U2") (pin "7") (pinfunction "AUX_CL_7") (pintype "bidirectional"))
    )
    (net (code "66") (name "unconnected-(U2-AUX_DA-Pad6)") (class "Default")
      (node (ref "U2") (pin "6") (pinfunction "AUX_DA_6") (pintype "bidirectional"))
    )
    (net (code "67") (name "unconnected-(U2-INT-Pad12)") (class "Default")
      (node (ref "U2") (pin "12") (pinfunction "INT_12") (pintype "bidirectional"))
    )
    (net (code "68") (name "unconnected-(U4-BP-Pad4)") (class "Default")
      (node (ref "U4") (pin "4") (pinfunction "BP_4") (pintype "input"))
    )
    (net (code "69") (name "unconnected-(U5-DRDY-Pad15)") (class "Default")
      (node (ref "U5") (pin "15") (pinfunction "DRDY_15") (pintype "bidirectional"))
    )
    (net (code "70") (name "unconnected-(U5-NC-Pad3)") (class "Default")
      (node (ref "U5") (pin "3") (pinfunction "NC_3") (pintype "bidirectional"))
    )
    (net (code "71") (name "unconnected-(U5-NC-Pad5)") (class "Default")
      (node (ref "U5") (pin "5") (pinfunction "NC_5") (pintype "bidirectional"))
    )
    (net (code "72") (name "unconnected-(U5-NC-Pad6)") (class "Default")
      (node (ref "U5") (pin "6") (pinfunction "NC_6") (pintype "bidirectional"))
    )
    (net (code "73") (name "unconnected-(U5-NC-Pad7)") (class "Default")
      (node (ref "U5") (pin "7") (pinfunction "NC_7") (pintype "bidirectional"))
    )
    (net (code "74") (name "unconnected-(U5-NC-Pad14)") (class "Default")
      (node (ref "U5") (pin "14") (pinfunction "NC_14") (pintype "bidirectional"))
    )
    (net (code "75") (name "unconnected-(U6-CSB-Pad1)") (class "Default")
      (node (ref "U6") (pin "1") (pinfunction "CSB_1") (pintype "bidirectional"))
    )
    (net (code "76") (name "unconnected-(U6-SDO-Pad4)") (class "Default")
      (node (ref "U6") (pin "4") (pinfunction "SDO_4") (pintype "bidirectional"))
    )
  )
)
